# 2_Microcontroller.net
KiCad netlist of a schematic drawn in Altium Designer
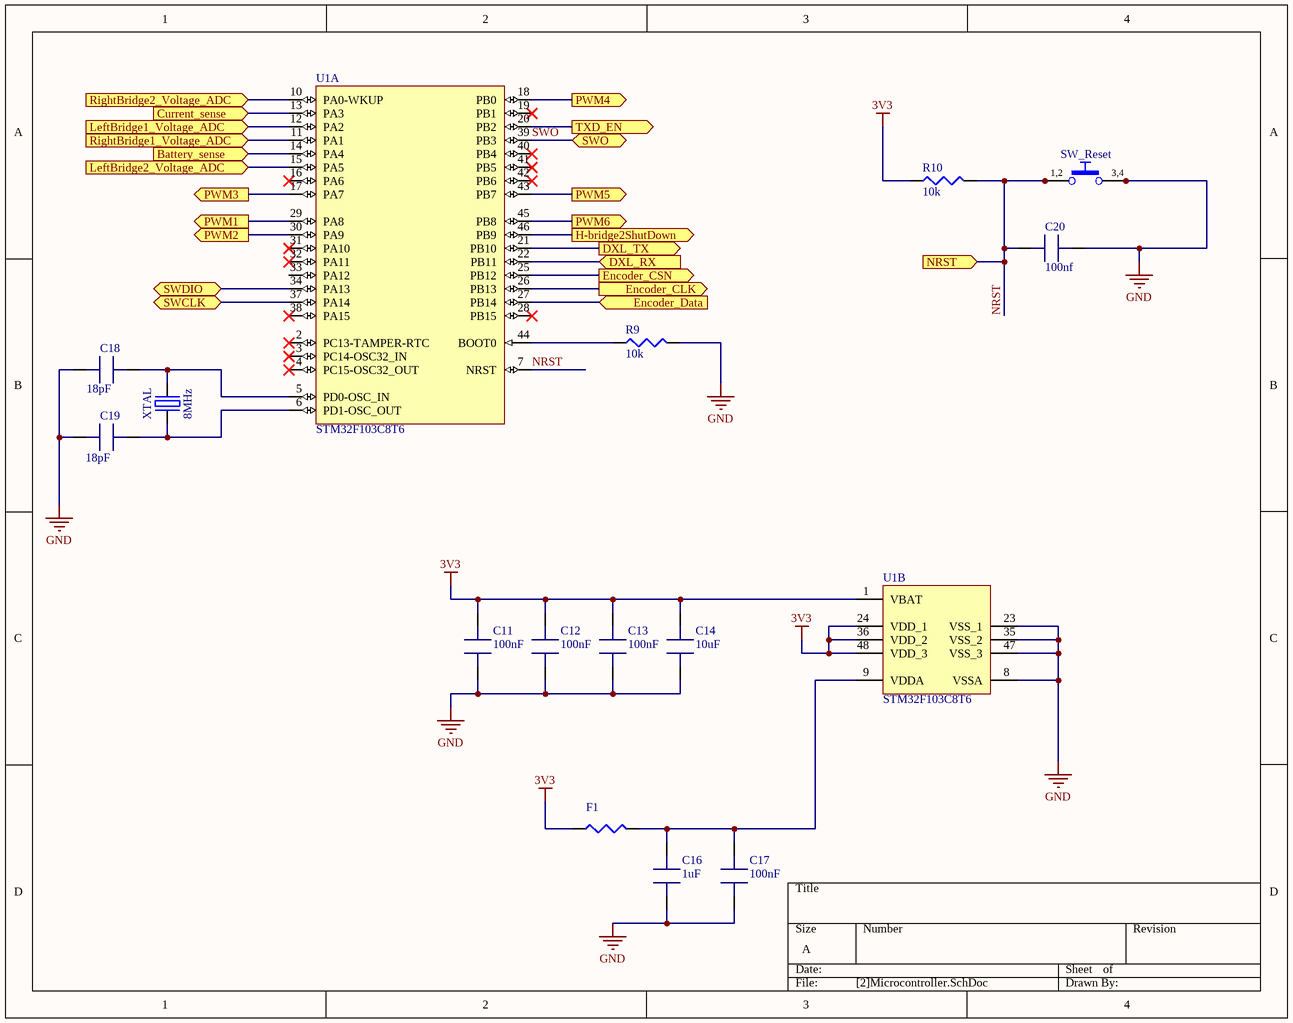
[diagram p0: [2]Microcontroller.SchDoc]

(export (version "E")
  (design (tool "Eeschema 10.0.6"))
  (components
    (comp (ref "C11") (value "100nF") (footprint "cap_805") (libsource (lib "CM") (part "cap805")))
    (comp (ref "C12") (value "100nF") (footprint "cap_805") (libsource (lib "CM") (part "cap805")))
    (comp (ref "C13") (value "100nF") (footprint "cap_805") (libsource (lib "CM") (part "cap805")))
    (comp (ref "C14") (value "10uF") (footprint "cap_805") (libsource (lib "CM") (part "cap805")))
    (comp (ref "C16") (value "1uF") (footprint "cap_805") (libsource (lib "CM") (part "cap805")))
    (comp (ref "C17") (value "100nF") (footprint "cap_805") (libsource (lib "CM") (part "cap805")))
    (comp (ref "C18") (value "18pF") (footprint "cap_805") (libsource (lib "CM") (part "cap805")))
    (comp (ref "C19") (value "18pF") (footprint "cap_805") (libsource (lib "CM") (part "cap805")))
    (comp (ref "C20") (value "100nf") (footprint "cap_805") (libsource (lib "CM") (part "cap805")))
    (comp (ref "F1") (value "Res805") (footprint "Res805") (libsource (lib "CM") (part "Res805")))
    (comp (ref "R9") (value "10k") (footprint "Res805") (libsource (lib "CM") (part "Res805")))
    (comp (ref "R10") (value "10k") (footprint "Res805") (libsource (lib "CM") (part "Res805")))
    (comp (ref "SW_Reset")
      (value "Push Button")
      (footprint "PB_OMRON_B3F-1000")
      (description "Push-Button Switch SPDT")
      (fields
        (field (name "PART NUMBER") "PB_OMRON_B3F-1000")
        (field (name "MANUFACTURER") "OMRON")
        (field (name "AUTHOR") "CERN DEM JMW")
      )
      (libsource (lib "Driver") (part "PB_OMRON_B3F-1000"))
    )
    (comp (ref "U1")
      (value "STM32F103C8T6")
      (footprint "STM-LQFP48_N")
      (libsource (lib "STMicroelectronics STM32 F1") (part "STM32F103C8T6"))
    )
    (comp (ref "XTAL")
      (value "8MHz")
      (footprint "XTAL_HC-49/U")
      (description "Quartz Crystal")
      (fields
        (field (name "PART NUMBER") "XTAL_20MHZ_AEL_HC-49/U")
        (field (name "MANUFACTURER") "AEL CRYSTALS")
        (field (name "AUTHOR") "CERN DEM JMW")
      )
      (libsource (lib "MotorDriver_Version1.0") (part "XTAL_20MHZ_AEL_HC-49/U"))
    )
  )
  (nets
    (net (code "1") (name "/Battery_sense") (class "Default")
      (node (ref "U1") (pin "14") (pinfunction "PA4_14") (pintype "bidirectional"))
    )
    (net (code "2") (name "/Current_sense") (class "Default")
      (node (ref "U1") (pin "13") (pinfunction "PA3_13") (pintype "bidirectional"))
    )
    (net (code "3") (name "/DXL_RX") (class "Default")
      (node (ref "U1") (pin "22") (pinfunction "PB11_22") (pintype "bidirectional"))
    )
    (net (code "4") (name "/DXL_TX") (class "Default")
      (node (ref "U1") (pin "21") (pinfunction "PB10_21") (pintype "bidirectional"))
    )
    (net (code "5") (name "/Encoder_CLK") (class "Default")
      (node (ref "U1") (pin "26") (pinfunction "PB13_26") (pintype "bidirectional"))
    )
    (net (code "6") (name "/Encoder_CSN") (class "Default")
      (node (ref "U1") (pin "25") (pinfunction "PB12_25") (pintype "bidirectional"))
    )
    (net (code "7") (name "/Encoder_Data") (class "Default")
      (node (ref "U1") (pin "27") (pinfunction "PB14_27") (pintype "bidirectional"))
    )
    (net (code "8") (name "/H-bridge2ShutDown") (class "Default")
      (node (ref "U1") (pin "46") (pinfunction "PB9_46") (pintype "bidirectional"))
    )
    (net (code "9") (name "/LeftBridge1_Voltage_ADC") (class "Default")
      (node (ref "U1") (pin "12") (pinfunction "PA2_12") (pintype "bidirectional"))
    )
    (net (code "10") (name "/LeftBridge2_Voltage_ADC") (class "Default")
      (node (ref "U1") (pin "15") (pinfunction "PA5_15") (pintype "bidirectional"))
    )
    (net (code "11") (name "/NRST") (class "Default")
      (node (ref "C20") (pin "1") (pinfunction "1_1") (pintype "passive"))
      (node (ref "R10") (pin "2") (pinfunction "2_2") (pintype "passive"))
      (node (ref "SW_Reset") (pin "1") (pinfunction "1_1") (pintype "passive"))
      (node (ref "SW_Reset") (pin "2") (pinfunction "2_2") (pintype "passive"))
      (node (ref "U1") (pin "7") (pinfunction "NRST_7") (pintype "bidirectional"))
    )
    (net (code "12") (name "/PWM1") (class "Default")
      (node (ref "U1") (pin "29") (pinfunction "PA8_29") (pintype "bidirectional"))
    )
    (net (code "13") (name "/PWM2") (class "Default")
      (node (ref "U1") (pin "30") (pinfunction "PA9_30") (pintype "bidirectional"))
    )
    (net (code "14") (name "/PWM3") (class "Default")
      (node (ref "U1") (pin "17") (pinfunction "PA7_17") (pintype "bidirectional"))
    )
    (net (code "15") (name "/PWM4") (class "Default")
      (node (ref "U1") (pin "18") (pinfunction "PB0_18") (pintype "bidirectional"))
    )
    (net (code "16") (name "/PWM5") (class "Default")
      (node (ref "U1") (pin "43") (pinfunction "PB7_43") (pintype "bidirectional"))
    )
    (net (code "17") (name "/PWM6") (class "Default")
      (node (ref "U1") (pin "45") (pinfunction "PB8_45") (pintype "bidirectional"))
    )
    (net (code "18") (name "/RightBridge1_Voltage_ADC") (class "Default")
      (node (ref "U1") (pin "11") (pinfunction "PA1_11") (pintype "bidirectional"))
    )
    (net (code "19") (name "/RightBridge2_Voltage_ADC") (class "Default")
      (node (ref "U1") (pin "10") (pinfunction "PA0-WKUP_10") (pintype "bidirectional"))
    )
    (net (code "20") (name "/SWCLK") (class "Default")
      (node (ref "U1") (pin "37") (pinfunction "PA14_37") (pintype "bidirectional"))
    )
    (net (code "21") (name "/SWDIO") (class "Default")
      (node (ref "U1") (pin "34") (pinfunction "PA13_34") (pintype "bidirectional"))
    )
    (net (code "22") (name "/SWO") (class "Default")
      (node (ref "U1") (pin "39") (pinfunction "PB3_39") (pintype "bidirectional"))
    )
    (net (code "23") (name "/TXD_EN") (class "Default")
      (node (ref "U1") (pin "20") (pinfunction "PB2_20") (pintype "bidirectional"))
    )
    (net (code "24") (name "3V3") (class "Default")
      (node (ref "C11") (pin "2") (pinfunction "2_2") (pintype "passive"))
      (node (ref "C12") (pin "2") (pinfunction "2_2") (pintype "passive"))
      (node (ref "C13") (pin "2") (pinfunction "2_2") (pintype "passive"))
      (node (ref "C14") (pin "2") (pinfunction "2_2") (pintype "passive"))
      (node (ref "F1") (pin "1") (pinfunction "1_1") (pintype "passive"))
      (node (ref "R10") (pin "1") (pinfunction "1_1") (pintype "passive"))
      (node (ref "U1") (pin "1") (pinfunction "VBAT_1") (pintype "power_in"))
      (node (ref "U1") (pin "24") (pinfunction "VDD_1_24") (pintype "power_in"))
      (node (ref "U1") (pin "36") (pinfunction "VDD_2_36") (pintype "power_in"))
      (node (ref "U1") (pin "48") (pinfunction "VDD_3_48") (pintype "power_in"))
    )
    (net (code "25") (name "GND") (class "Default")
      (node (ref "C11") (pin "1") (pinfunction "1_1") (pintype "passive"))
      (node (ref "C12") (pin "1") (pinfunction "1_1") (pintype "passive"))
      (node (ref "C13") (pin "1") (pinfunction "1_1") (pintype "passive"))
      (node (ref "C14") (pin "1") (pinfunction "1_1") (pintype "passive"))
      (node (ref "C16") (pin "1") (pinfunction "1_1") (pintype "passive"))
      (node (ref "C17") (pin "1") (pinfunction "1_1") (pintype "passive"))
      (node (ref "C18") (pin "1") (pinfunction "1_1") (pintype "passive"))
      (node (ref "C19") (pin "1") (pinfunction "1_1") (pintype "passive"))
      (node (ref "C20") (pin "2") (pinfunction "2_2") (pintype "passive"))
      (node (ref "R9") (pin "2") (pinfunction "2_2") (pintype "passive"))
      (node (ref "SW_Reset") (pin "3") (pinfunction "3_3") (pintype "passive"))
      (node (ref "SW_Reset") (pin "4") (pinfunction "4_4") (pintype "passive"))
      (node (ref "U1") (pin "23") (pinfunction "VSS_1_23") (pintype "power_in"))
      (node (ref "U1") (pin "35") (pinfunction "VSS_2_35") (pintype "power_in"))
      (node (ref "U1") (pin "47") (pinfunction "VSS_3_47") (pintype "power_in"))
      (node (ref "U1") (pin "8") (pinfunction "VSSA_8") (pintype "power_in"))
    )
    (net (code "26") (name "Net-(U1A-BOOT0)") (class "Default")
      (node (ref "R9") (pin "1") (pinfunction "1_1") (pintype "passive"))
      (node (ref "U1") (pin "44") (pinfunction "BOOT0_44") (pintype "input"))
    )
    (net (code "27") (name "Net-(U1A-PD0-OSC_IN)") (class "Default")
      (node (ref "C18") (pin "2") (pinfunction "2_2") (pintype "passive"))
      (node (ref "U1") (pin "5") (pinfunction "PD0-OSC_IN_5") (pintype "bidirectional"))
      (node (ref "XTAL") (pin "2") (pinfunction "OSC2_2") (pintype "passive"))
    )
    (net (code "28") (name "Net-(U1A-PD1-OSC_OUT)") (class "Default")
      (node (ref "C19") (pin "2") (pinfunction "2_2") (pintype "passive"))
      (node (ref "U1") (pin "6") (pinfunction "PD1-OSC_OUT_6") (pintype "bidirectional"))
      (node (ref "XTAL") (pin "1") (pinfunction "OSC1_1") (pintype "passive"))
    )
    (net (code "29") (name "Net-(U1B-VDDA)") (class "Default")
      (node (ref "C16") (pin "2") (pinfunction "2_2") (pintype "passive"))
      (node (ref "C17") (pin "2") (pinfunction "2_2") (pintype "passive"))
      (node (ref "F1") (pin "2") (pinfunction "2_2") (pintype "passive"))
      (node (ref "U1") (pin "9") (pinfunction "VDDA_9") (pintype "power_in"))
    )
    (net (code "30") (name "unconnected-(U1A-PA6-Pad16)") (class "Default")
      (node (ref "U1") (pin "16") (pinfunction "PA6_16") (pintype "bidirectional+no_connect"))
    )
    (net (code "31") (name "unconnected-(U1A-PA10-Pad31)") (class "Default")
      (node (ref "U1") (pin "31") (pinfunction "PA10_31") (pintype "bidirectional+no_connect"))
    )
    (net (code "32") (name "unconnected-(U1A-PA11-Pad32)") (class "Default")
      (node (ref "U1") (pin "32") (pinfunction "PA11_32") (pintype "bidirectional+no_connect"))
    )
    (net (code "33") (name "unconnected-(U1A-PA12-Pad33)") (class "Default")
      (node (ref "U1") (pin "33") (pinfunction "PA12_33") (pintype "bidirectional"))
    )
    (net (code "34") (name "unconnected-(U1A-PA15-Pad38)") (class "Default")
      (node (ref "U1") (pin "38") (pinfunction "PA15_38") (pintype "bidirectional+no_connect"))
    )
    (net (code "35") (name "unconnected-(U1A-PB1-Pad19)") (class "Default")
      (node (ref "U1") (pin "19") (pinfunction "PB1_19") (pintype "bidirectional+no_connect"))
    )
    (net (code "36") (name "unconnected-(U1A-PB4-Pad40)") (class "Default")
      (node (ref "U1") (pin "40") (pinfunction "PB4_40") (pintype "bidirectional+no_connect"))
    )
    (net (code "37") (name "unconnected-(U1A-PB5-Pad41)") (class "Default")
      (node (ref "U1") (pin "41") (pinfunction "PB5_41") (pintype "bidirectional+no_connect"))
    )
    (net (code "38") (name "unconnected-(U1A-PB6-Pad42)") (class "Default")
      (node (ref "U1") (pin "42") (pinfunction "PB6_42") (pintype "bidirectional+no_connect"))
    )
    (net (code "39") (name "unconnected-(U1A-PB15-Pad28)") (class "Default")
      (node (ref "U1") (pin "28") (pinfunction "PB15_28") (pintype "bidirectional+no_connect"))
    )
    (net (code "40") (name "unconnected-(U1A-PC13-TAMPER-RTC-Pad2)") (class "Default")
      (node (ref "U1") (pin "2") (pinfunction "PC13-TAMPER-RTC_2") (pintype "bidirectional+no_connect"))
    )
    (net (code "41") (name "unconnected-(U1A-PC14-OSC32_IN-Pad3)") (class "Default")
      (node (ref "U1") (pin "3") (pinfunction "PC14-OSC32_IN_3") (pintype "bidirectional+no_connect"))
    )
    (net (code "42") (name "unconnected-(U1A-PC15-OSC32_OUT-Pad4)") (class "Default")
      (node (ref "U1") (pin "4") (pinfunction "PC15-OSC32_OUT_4") (pintype "bidirectional+no_connect"))
    )
  )
)
